# MB_ps_io.net
KiCad netlist of a schematic drawn in Altium Designer
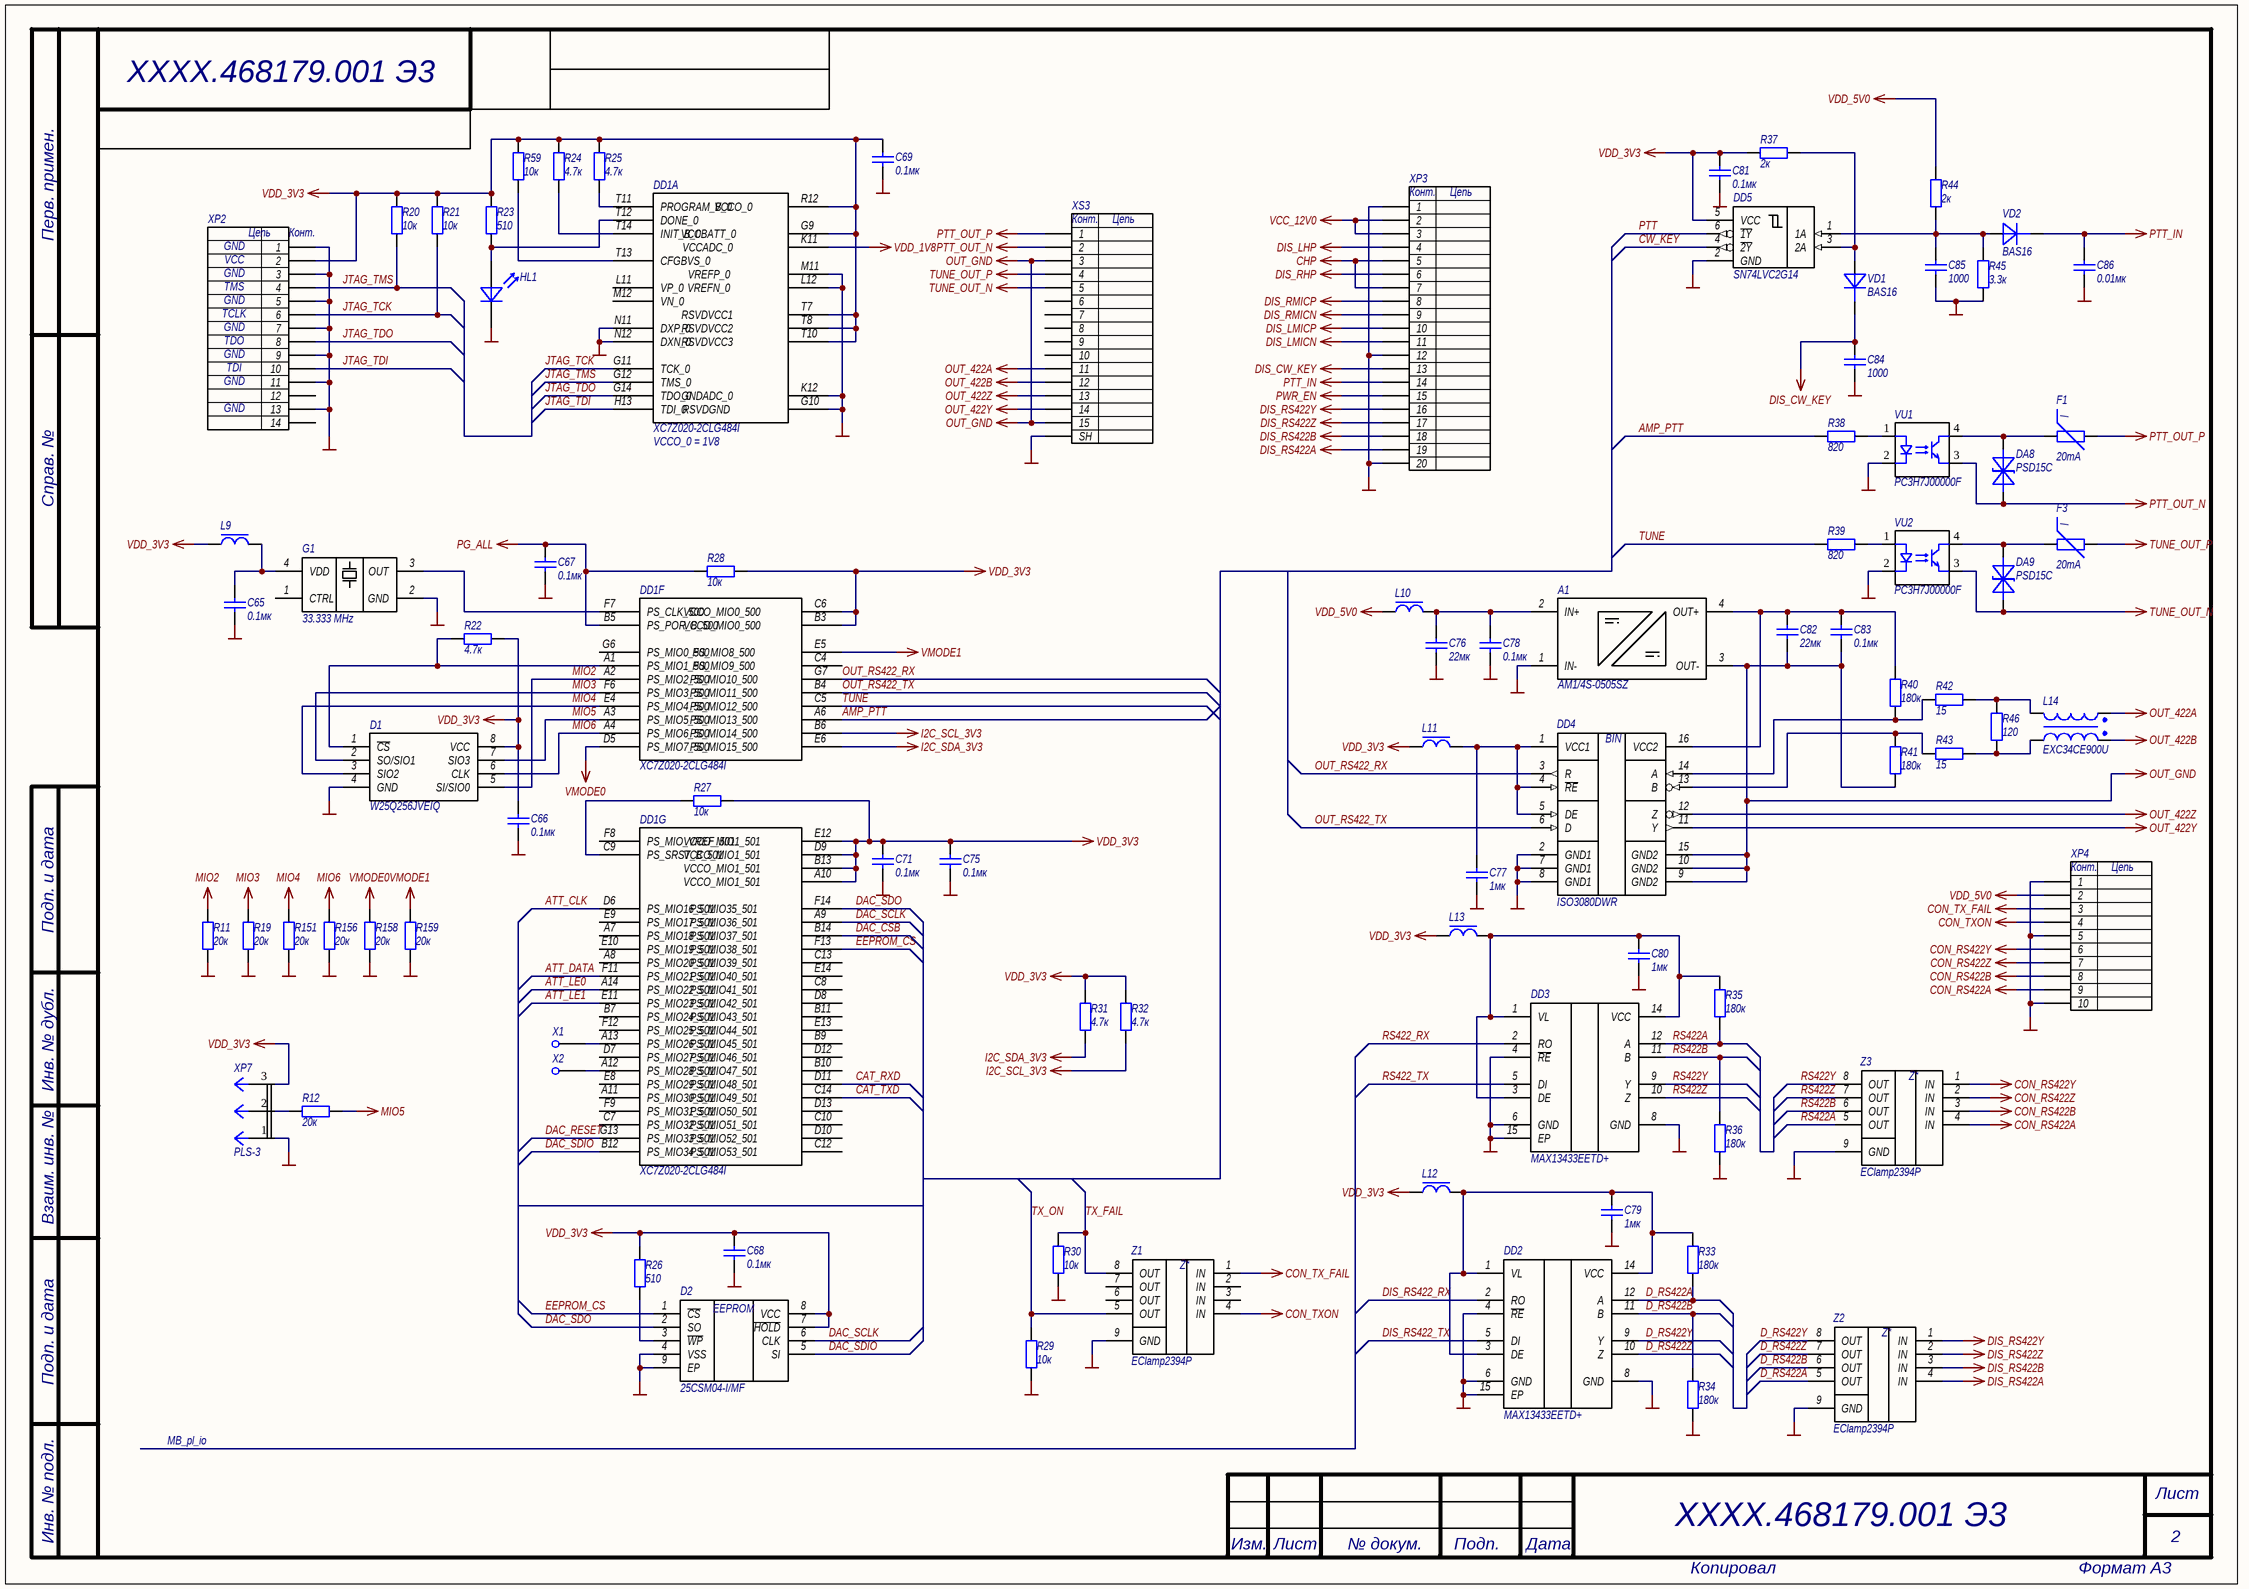
[diagram p0: MB_ps_io.SchDoc]

(export (version "E")
  (design (tool "Eeschema 10.0.6"))
  (components
    (comp (ref "A1")
      (value "AM1/4S-0505SZ")
      (footprint "Series AM1/4S-Z")
      (description "0.25 Watt ¦ DC-DC Converter")
      (fields (field (name "MANUFACTURER") "flex"))
      (libsource (lib "nels_other") (part "Модуль AM1/4S-0505SZ"))
    )
    (comp (ref "C65")
      (value "0.1мк")
      (footprint "CAPC1005X06N")
      (description "Кер. ЧИП-конденсатор")
      (fields (field (name "TOLERANCE") "±10%"))
      (libsource (lib "nels") (part "Кер.ЧИП конд. 0402 0.1мкФ X7R 10%, 16В"))
    )
    (comp (ref "C66")
      (value "0.1мк")
      (footprint "CAPC1005X06N")
      (description "Кер. ЧИП-конденсатор")
      (fields (field (name "TOLERANCE") "±10%"))
      (libsource (lib "nels") (part "Кер.ЧИП конд. 0402 0.1мкФ X7R 10%, 16В"))
    )
    (comp (ref "C67")
      (value "0.1мк")
      (footprint "CAPC1005X06N")
      (description "Кер. ЧИП-конденсатор")
      (fields (field (name "TOLERANCE") "±10%"))
      (libsource (lib "nels") (part "Кер.ЧИП конд. 0402 0.1мкФ X7R 10%, 16В"))
    )
    (comp (ref "C68")
      (value "0.1мк")
      (footprint "CAPC1005X06N")
      (description "Кер. ЧИП-конденсатор")
      (fields (field (name "TOLERANCE") "±10%"))
      (libsource (lib "nels") (part "Кер.ЧИП конд. 0402 0.1мкФ X7R 10%, 16В"))
    )
    (comp (ref "C69")
      (value "0.1мк")
      (footprint "CAPC1005X06N")
      (description "Кер. ЧИП-конденсатор")
      (fields (field (name "TOLERANCE") "±10%"))
      (libsource (lib "nels") (part "Кер.ЧИП конд. 0402 0.1мкФ X7R 10%, 16В"))
    )
    (comp (ref "C71")
      (value "0.1мк")
      (footprint "CAPC1005X06N")
      (description "Кер. ЧИП-конденсатор")
      (fields (field (name "TOLERANCE") "±10%"))
      (libsource (lib "nels") (part "Кер.ЧИП конд. 0402 0.1мкФ X7R 10%, 16В"))
    )
    (comp (ref "C75")
      (value "0.1мк")
      (footprint "CAPC1005X06N")
      (description "Кер. ЧИП-конденсатор")
      (fields (field (name "TOLERANCE") "±10%"))
      (libsource (lib "nels") (part "Кер.ЧИП конд. 0402 0.1мкФ X7R 10%, 16В"))
    )
    (comp (ref "C76")
      (value "22мк")
      (footprint "CAPC2012X12L")
      (description "Кер. ЧИП-конденсатор")
      (fields (field (name "MANUFACTURER") "TDK") (field (name "TOLERANCE") "±10%"))
      (libsource (lib "nels_caps") (part "Кер.ЧИП конд. 0805 22мкФ X5R 10% 16В"))
    )
    (comp (ref "C77")
      (value "1мк")
      (footprint "CAPC1005X06N")
      (description "Кер. ЧИП-конденсатор")
      (fields (field (name "TOLERANCE") "±10%"))
      (libsource (lib "nels_caps") (part "Кер.ЧИП конд. 0402 1мкФ X5R 10%, 10В"))
    )
    (comp (ref "C78")
      (value "0.1мк")
      (footprint "CAPC1005X06N")
      (description "Кер. ЧИП-конденсатор")
      (fields (field (name "TOLERANCE") "±10%"))
      (libsource (lib "nels") (part "Кер.ЧИП конд. 0402 0.1мкФ X7R 10%, 16В"))
    )
    (comp (ref "C79")
      (value "1мк")
      (footprint "CAPC1005X06N")
      (description "Кер. ЧИП-конденсатор")
      (fields (field (name "TOLERANCE") "±10%"))
      (libsource (lib "nels_caps") (part "Кер.ЧИП конд. 0402 1мкФ X5R 10%, 10В"))
    )
    (comp (ref "C80")
      (value "1мк")
      (footprint "CAPC1005X06N")
      (description "Кер. ЧИП-конденсатор")
      (fields (field (name "TOLERANCE") "±10%"))
      (libsource (lib "nels_caps") (part "Кер.ЧИП конд. 0402 1мкФ X5R 10%, 10В"))
    )
    (comp (ref "C81")
      (value "0.1мк")
      (footprint "CAPC1005X06N")
      (description "Кер. ЧИП-конденсатор")
      (fields (field (name "TOLERANCE") "±10%"))
      (libsource (lib "nels") (part "Кер.ЧИП конд. 0402 0.1мкФ X7R 10%, 16В"))
    )
    (comp (ref "C82")
      (value "22мк")
      (footprint "CAPC2012X12L")
      (description "Кер. ЧИП-конденсатор")
      (fields (field (name "MANUFACTURER") "TDK") (field (name "TOLERANCE") "±10%"))
      (libsource (lib "nels_caps") (part "Кер.ЧИП конд. 0805 22мкФ X5R 10% 16В"))
    )
    (comp (ref "C83")
      (value "0.1мк")
      (footprint "CAPC1005X06N")
      (description "Кер. ЧИП-конденсатор")
      (fields (field (name "TOLERANCE") "±10%"))
      (libsource (lib "nels") (part "Кер.ЧИП конд. 0402 0.1мкФ X7R 10%, 16В"))
    )
    (comp (ref "C84")
      (value "1000")
      (footprint "CAPC1005X06N")
      (description "Кер. ЧИП-конденсатор")
      (fields (field (name "TOLERANCE") "±5%"))
      (libsource (lib "nels_caps") (part "Кер.ЧИП конд. 0402 1000пФ NP0 5%, 50В"))
    )
    (comp (ref "C85")
      (value "1000")
      (footprint "CAPC1005X06N")
      (description "Кер. ЧИП-конденсатор")
      (fields (field (name "TOLERANCE") "±5%"))
      (libsource (lib "nels_caps") (part "Кер.ЧИП конд. 0402 1000пФ NP0 5%, 50В"))
    )
    (comp (ref "C86")
      (value "0.01мк")
      (footprint "CAPC1005X06N")
      (description "Кер. ЧИП-конденсатор")
      (fields (field (name "TOLERANCE") "±20%"))
      (libsource (lib "nels_caps") (part "Кер.ЧИП конд. 0402 0.01мкФ X7R 10%, 50В"))
    )
    (comp (ref "D1")
      (value "W25Q256JVEIQ")
      (footprint "SON127P800X70_HS-9N")
      (description "3V 256M-BIT SERIAL FLASH MEMORY WITH DUAL/QUAD SPI")
      (fields (field (name "MANUFACTURER") "WINBOND"))
      (libsource (lib "nels_chip") (part "Микросхема W25Q256JVEIQ"))
    )
    (comp (ref "D2")
      (value "25CSM04-I/MF")
      (footprint "SON127P600X80_HS-9N")
      (description "4-Mbit SPI Serial EEPROM with 128-Bit Serial Number and Enhanced Write Protection")
      (fields (field (name "MANUFACTURER") "MICROCHIP"))
      (libsource (lib "nels_chip") (part "Микросхема 25CSM04-I/MF"))
    )
    (comp (ref "DA8")
      (value "PSD15C")
      (footprint "SOT0P254X110-2N")
      (description "HIGH POWERED TVS")
      (fields (field (name "MANUFACTURER") "PROTEK"))
      (libsource (lib "nels_other") (part "ЧИП защитный диод PSD15C"))
    )
    (comp (ref "DA9")
      (value "PSD15C")
      (footprint "SOT0P254X110-2N")
      (description "HIGH POWERED TVS")
      (fields (field (name "MANUFACTURER") "PROTEK"))
      (libsource (lib "nels_other") (part "ЧИП защитный диод PSD15C"))
    )
    (comp (ref "DD1")
      (value "XC7Z020-2CLG484I")
      (footprint "BGA484C80P22X22_1900X1900X160")
      (description "Zynq®-7000 SoC Family")
      (fields (field (name "MANUFACTURER") "XILINX"))
      (libsource (lib "MB") (part "Микросхема XC7Z020-2CLG484I"))
    )
    (comp (ref "DD2")
      (value "MAX13433EETD+")
      (footprint "SON40P300X80_HS-15L")
      (description "RS-422 Transceivers with Low-Voltage Logic Interface 16M")
      (fields (field (name "MANUFACTURER") "Maxim"))
      (libsource (lib "nels_chip") (part "Микросхема MAX13433EETD+"))
    )
    (comp (ref "DD3")
      (value "MAX13433EETD+")
      (footprint "SON40P300X80_HS-15L")
      (description "RS-422 Transceivers with Low-Voltage Logic Interface 16M")
      (fields (field (name "MANUFACTURER") "Maxim"))
      (libsource (lib "nels_chip") (part "Микросхема MAX13433EETD+"))
    )
    (comp (ref "DD4")
      (value "ISO3080DWR")
      (footprint "SOIC127P1030X265-16N")
      (description "ISOLATED 5-V FULL DUPLEX RS-485 TRANSCEIVERS 200 kbps")
      (fields (field (name "MANUFACTURER") "TI"))
      (libsource (lib "nels_chip") (part "Микросхема ISO3080DWR"))
    )
    (comp (ref "DD5")
      (value "SN74LVC2G14")
      (footprint "SOT65P210X110-6L")
      (description "Dual Schmitt-Trigger Inverter")
      (fields (field (name "MANUFACTURER") "TI"))
      (libsource (lib "nels_chip") (part "Микросхема SN74LVC2G14DCKR"))
    )
    (comp (ref "F1")
      (value "20mA")
      (footprint "FUSC1607X85N")
      (description "ЧИП-резистор")
      (fields (field (name "MANUFACTURER") "Belfuse") (field (name "MANUFACTURERPARTNUMBER") "0ZCM0002FF2G"))
      (libsource (lib "nels_other") (part "Чип предохранитель 0ZCM0002FF2G"))
    )
    (comp (ref "F3")
      (value "20mA")
      (footprint "FUSC1607X85N")
      (description "ЧИП-резистор")
      (fields (field (name "MANUFACTURER") "Belfuse") (field (name "MANUFACTURERPARTNUMBER") "0ZCM0002FF2G"))
      (libsource (lib "nels_other") (part "Чип предохранитель 0ZCM0002FF2G"))
    )
    (comp (ref "G1")
      (value "33.333 MHz")
      (footprint "XTAL_ASFLMB-33.333MHZ-LC-T")
      (description "33.333 MHz HCMOS/TTL Clock Oscillator")
      (fields (field (name "MANUFACTURER") "Abracom"))
      (libsource (lib "nels_other") (part "Генератор кварцевый ASFLMB-33.333MHZ"))
    )
    (comp (ref "HL1")
      (value "~")
      (footprint "CD1608-0603_GREEN")
      (description "ЧИП-светодиод")
      (fields
        (field (name "MANUFACTURER") "FORYARD")
        (field (name "MANUFACTURERPARTNUMBER") "FYLS-0603UGC")
        (field (name "PUBLISHER") "Altium Limited")
      )
      (libsource (lib "nels_other") (part "Светодиод SMD FYLS-0603UGC (зеленый)"))
    )
    (comp (ref "L9")
      (value "BLM18PG121SN1D")
      (footprint "INDC1608X08L")
      (description "SMD EMI Suppression Filter EMIFIL")
      (fields (field (name "MANUFACTURER") "Murata"))
      (libsource (lib "nels_ind") (part "ЧИП дроссель 0603 BLM18PG121SN1D"))
    )
    (comp (ref "L10")
      (value "BLM18PG121SN1D")
      (footprint "INDC1608X08L")
      (description "SMD EMI Suppression Filter EMIFIL")
      (fields (field (name "MANUFACTURER") "Murata"))
      (libsource (lib "nels_ind") (part "ЧИП дроссель 0603 BLM18PG121SN1D"))
    )
    (comp (ref "L11")
      (value "BLM18PG121SN1D")
      (footprint "INDC1608X08L")
      (description "SMD EMI Suppression Filter EMIFIL")
      (fields (field (name "MANUFACTURER") "Murata"))
      (libsource (lib "nels_ind") (part "ЧИП дроссель 0603 BLM18PG121SN1D"))
    )
    (comp (ref "L12")
      (value "BLM18PG121SN1D")
      (footprint "INDC1608X08L")
      (description "SMD EMI Suppression Filter EMIFIL")
      (fields (field (name "MANUFACTURER") "Murata"))
      (libsource (lib "nels_ind") (part "ЧИП дроссель 0603 BLM18PG121SN1D"))
    )
    (comp (ref "L13")
      (value "BLM18PG121SN1D")
      (footprint "INDC1608X08L")
      (description "SMD EMI Suppression Filter EMIFIL")
      (fields (field (name "MANUFACTURER") "Murata"))
      (libsource (lib "nels_ind") (part "ЧИП дроссель 0603 BLM18PG121SN1D"))
    )
    (comp (ref "L14")
      (value "EXC34CE900U")
      (footprint "EXC34CE900U")
      (description "Common Mode Noise Filters EXC34CG/CE type")
      (fields (field (name "MANUFACTURER") "Panasonic"))
      (libsource (lib "nels_ind") (part "ЧИП синфазный фильтр 0805 EXC34CE900U"))
    )
    (comp (ref "R11")
      (value "20к")
      (footprint "RESC1005X06N")
      (description "ЧИП-резистор")
      (fields (field (name "TOLERANCE") "±5%"))
      (libsource (lib "nels_res") (part "Чип резистор 0402 20 кОм, 5%"))
    )
    (comp (ref "R12")
      (value "20к")
      (footprint "RESC1005X06N")
      (description "ЧИП-резистор")
      (fields (field (name "TOLERANCE") "±5%"))
      (libsource (lib "") (part "Чип резистор 0402 20 кОм, 5%_1"))
    )
    (comp (ref "R19")
      (value "20к")
      (footprint "RESC1005X06N")
      (description "ЧИП-резистор")
      (fields (field (name "TOLERANCE") "±5%"))
      (libsource (lib "nels_res") (part "Чип резистор 0402 20 кОм, 5%"))
    )
    (comp (ref "R20")
      (value "10к")
      (footprint "RESC1005X06N")
      (description "ЧИП-резистор")
      (fields (field (name "TOLERANCE") "±5%"))
      (libsource (lib "") (part "Чип резистор 0402 10 кОм, 5%_2"))
    )
    (comp (ref "R21")
      (value "10к")
      (footprint "RESC1005X06N")
      (description "ЧИП-резистор")
      (fields (field (name "TOLERANCE") "±5%"))
      (libsource (lib "") (part "Чип резистор 0402 10 кОм, 5%_2"))
    )
    (comp (ref "R22")
      (value "4.7к")
      (footprint "RESC1005X06N")
      (description "ЧИП-резистор")
      (fields (field (name "TOLERANCE") "±5%"))
      (libsource (lib "nels_res") (part "Чип резистор 0402 4,7 кОм, 5%"))
    )
    (comp (ref "R23")
      (value "510")
      (footprint "RESC1005X06N")
      (description "ЧИП-резистор")
      (fields (field (name "TOLERANCE") "±5%"))
      (libsource (lib "nels_res") (part "Чип резистор 0402 510 Ом, 5%"))
    )
    (comp (ref "R24")
      (value "4.7к")
      (footprint "RESC1005X06N")
      (description "ЧИП-резистор")
      (fields (field (name "TOLERANCE") "±1%"))
      (libsource (lib "nels_res") (part "Чип резистор 0402 4,7 кОм, 1%"))
    )
    (comp (ref "R25")
      (value "4.7к")
      (footprint "RESC1005X06N")
      (description "ЧИП-резистор")
      (fields (field (name "TOLERANCE") "±1%"))
      (libsource (lib "nels_res") (part "Чип резистор 0402 4,7 кОм, 1%"))
    )
    (comp (ref "R26")
      (value "510")
      (footprint "RESC1005X06N")
      (description "ЧИП-резистор")
      (fields (field (name "TOLERANCE") "±5%"))
      (libsource (lib "nels_res") (part "Чип резистор 0402 510 Ом, 5%"))
    )
    (comp (ref "R27")
      (value "10к")
      (footprint "RESC1005X06N")
      (description "ЧИП-резистор")
      (fields (field (name "TOLERANCE") "±5%"))
      (libsource (lib "") (part "Чип резистор 0402 10 кОм, 5%_1"))
    )
    (comp (ref "R28")
      (value "10к")
      (footprint "RESC1005X06N")
      (description "ЧИП-резистор")
      (fields (field (name "TOLERANCE") "±5%"))
      (libsource (lib "") (part "Чип резистор 0402 10 кОм, 5%_1"))
    )
    (comp (ref "R29")
      (value "10к")
      (footprint "RESC1005X06N")
      (description "ЧИП-резистор")
      (fields (field (name "TOLERANCE") "±5%"))
      (libsource (lib "nels") (part "Чип резистор 0402 10 кОм, 5%"))
    )
    (comp (ref "R30")
      (value "10к")
      (footprint "RESC1005X06N")
      (description "ЧИП-резистор")
      (fields (field (name "TOLERANCE") "±5%"))
      (libsource (lib "nels") (part "Чип резистор 0402 10 кОм, 5%"))
    )
    (comp (ref "R31")
      (value "4.7к")
      (footprint "RESC1005X06N")
      (description "ЧИП-резистор")
      (fields (field (name "TOLERANCE") "±5%"))
      (libsource (lib "") (part "Чип резистор 0402 4,7 кОм, 5%_1"))
    )
    (comp (ref "R32")
      (value "4.7к")
      (footprint "RESC1005X06N")
      (description "ЧИП-резистор")
      (fields (field (name "TOLERANCE") "±5%"))
      (libsource (lib "") (part "Чип резистор 0402 4,7 кОм, 5%_1"))
    )
    (comp (ref "R33")
      (value "180к")
      (footprint "RESC1005X06N")
      (description "ЧИП-резистор")
      (fields (field (name "TOLERANCE") "±5%"))
      (libsource (lib "nels") (part "Чип резистор 0402 180 кОм, 5%"))
    )
    (comp (ref "R34")
      (value "180к")
      (footprint "RESC1005X06N")
      (description "ЧИП-резистор")
      (fields (field (name "TOLERANCE") "±5%"))
      (libsource (lib "nels") (part "Чип резистор 0402 180 кОм, 5%"))
    )
    (comp (ref "R35")
      (value "180к")
      (footprint "RESC1005X06N")
      (description "ЧИП-резистор")
      (fields (field (name "TOLERANCE") "±5%"))
      (libsource (lib "nels") (part "Чип резистор 0402 180 кОм, 5%"))
    )
    (comp (ref "R36")
      (value "180к")
      (footprint "RESC1005X06N")
      (description "ЧИП-резистор")
      (fields (field (name "TOLERANCE") "±5%"))
      (libsource (lib "nels") (part "Чип резистор 0402 180 кОм, 5%"))
    )
    (comp (ref "R37")
      (value "2к")
      (footprint "RESC1005X06N")
      (description "ЧИП-резистор")
      (fields (field (name "TOLERANCE") "±5%"))
      (libsource (lib "") (part "Чип резистор 0402 2 кОм, 5%_1"))
    )
    (comp (ref "R38")
      (value "820")
      (footprint "RESC1005X06N")
      (description "ЧИП-резистор")
      (fields (field (name "TOLERANCE") "±5%"))
      (libsource (lib "nels_res") (part "Чип резистор 0402 820 Ом, 5%"))
    )
    (comp (ref "R39")
      (value "820")
      (footprint "RESC1005X06N")
      (description "ЧИП-резистор")
      (fields (field (name "TOLERANCE") "±5%"))
      (libsource (lib "nels_res") (part "Чип резистор 0402 820 Ом, 5%"))
    )
    (comp (ref "R40")
      (value "180к")
      (footprint "RESC1005X06N")
      (description "ЧИП-резистор")
      (fields (field (name "TOLERANCE") "±5%"))
      (libsource (lib "nels") (part "Чип резистор 0402 180 кОм, 5%"))
    )
    (comp (ref "R41")
      (value "180к")
      (footprint "RESC1005X06N")
      (description "ЧИП-резистор")
      (fields (field (name "TOLERANCE") "±5%"))
      (libsource (lib "nels") (part "Чип резистор 0402 180 кОм, 5%"))
    )
    (comp (ref "R42")
      (value "15")
      (footprint "RESC1005X06N")
      (description "ЧИП-резистор")
      (fields (field (name "TOLERANCE") "±5%"))
      (libsource (lib "nels") (part "Чип резистор 0402 15 Ом, 5%"))
    )
    (comp (ref "R43")
      (value "15")
      (footprint "RESC1005X06N")
      (description "ЧИП-резистор")
      (fields (field (name "TOLERANCE") "±5%"))
      (libsource (lib "nels") (part "Чип резистор 0402 15 Ом, 5%"))
    )
    (comp (ref "R44")
      (value "2к")
      (footprint "RESC1005X06N")
      (description "ЧИП-резистор")
      (fields (field (name "TOLERANCE") "±5%"))
      (libsource (lib "nels_res") (part "Чип резистор 0402 2 кОм, 5%"))
    )
    (comp (ref "R45")
      (value "3.3к")
      (footprint "RESC1005X06N")
      (description "ЧИП-резистор")
      (fields (field (name "TOLERANCE") "±5%"))
      (libsource (lib "nels_res") (part "Чип резистор 0402 3,3 кОм, 5%"))
    )
    (comp (ref "R46")
      (value "120")
      (footprint "RESC1005X06N")
      (description "ЧИП-резистор")
      (fields (field (name "TOLERANCE") "±5%"))
      (libsource (lib "nels") (part "Чип резистор 0402 120 Ом, 5%"))
    )
    (comp (ref "R59")
      (value "10к")
      (footprint "RESC1005X06N")
      (description "ЧИП-резистор")
      (fields (field (name "TOLERANCE") "±5%"))
      (libsource (lib "nels") (part "Чип резистор 0402 10 кОм, 5%"))
    )
    (comp (ref "R151")
      (value "20к")
      (footprint "RESC1005X06N")
      (description "ЧИП-резистор")
      (fields (field (name "TOLERANCE") "±5%"))
      (libsource (lib "nels_res") (part "Чип резистор 0402 20 кОм, 5%"))
    )
    (comp (ref "R156")
      (value "20к")
      (footprint "RESC1005X06N")
      (description "ЧИП-резистор")
      (fields (field (name "TOLERANCE") "±5%"))
      (libsource (lib "nels_res") (part "Чип резистор 0402 20 кОм, 5%"))
    )
    (comp (ref "R158")
      (value "20к")
      (footprint "RESC1005X06N")
      (description "ЧИП-резистор")
      (fields (field (name "TOLERANCE") "±5%"))
      (libsource (lib "nels_res") (part "Чип резистор 0402 20 кОм, 5%"))
    )
    (comp (ref "R159")
      (value "20к")
      (footprint "RESC1005X06N")
      (description "ЧИП-резистор")
      (fields (field (name "TOLERANCE") "±5%"))
      (libsource (lib "nels_res") (part "Чип резистор 0402 20 кОм, 5%"))
    )
    (comp (ref "VD1")
      (value "BAS16")
      (footprint "SOT23_N")
      (description "High-speed switching diodes")
      (fields (field (name "MANUFACTURER") "Nexperia"))
      (libsource (lib "nels_other") (part "ЧИП диод BAS16"))
    )
    (comp (ref "VD2")
      (value "BAS16")
      (footprint "SOT23_N")
      (description "High-speed switching diodes")
      (fields (field (name "MANUFACTURER") "Nexperia"))
      (libsource (lib "nels_other") (part "ЧИП диод BAS16"))
    )
    (comp (ref "VU1")
      (value "PC3H7J00000F")
      (footprint "SO4-170-1.27")
      (description "Mini-falt Package, General Purpose Half Pitch Photocouper")
      (libsource (lib "nels_other") (part "Оптопара транзисторная PC3H7J00000F"))
    )
    (comp (ref "VU2")
      (value "PC3H7J00000F")
      (footprint "SO4-170-1.27")
      (description "Mini-falt Package, General Purpose Half Pitch Photocouper")
      (libsource (lib "nels_other") (part "Оптопара транзисторная PC3H7J00000F"))
    )
    (comp (ref "X1")
      (value "Конструктивный элемент")
      (footprint "PIN2_PROBE")
      (description "Соединитель")
      (libsource (lib "nels_conn") (part "Соединение под пайку"))
    )
    (comp (ref "X2")
      (value "Конструктивный элемент")
      (footprint "PIN2_PROBE")
      (description "Соединитель")
      (libsource (lib "nels_conn") (part "Соединение под пайку"))
    )
    (comp (ref "XP2")
      (value "IDC2-14MS")
      (footprint "IDC2-14MS")
      (description "JTAG Xilinx IDC2-14MS")
      (fields (field (name "MANUFACTURER") "Molex"))
      (libsource (lib "nels") (part "Соединитель IDC2-14MS"))
    )
    (comp (ref "XP3")
      (value "FH12-20S-0.5SVA")
      (footprint "FH12-20S-0.5SVA")
      (description "FPC Connectors, Flex-to-Board, 20 Position, .5mm [.02in]")
      (libsource (lib "nels_conn") (part "Соединитель FH12-20S-0.5SVA"))
    )
    (comp (ref "XP4")
      (value "FH12-10S-0.5SVA")
      (footprint "FH12-10S-0.5SH")
      (description "0.5mm  Pitch FPC/FFC Connector FH12 Series")
      (fields (field (name "MANUFACTURER") "Hirose"))
      (libsource (lib "nels_conn") (part "Соединитель FH12-10S-0.5SVA"))
    )
    (comp (ref "XP7")
      (value "PLS-3")
      (footprint "PLS-3 (DS1021-1x3)")
      (description "Вилка штыревая 2.54мм 1x3 прямая тип1")
      (libsource (lib "nels_conn") (part "Соединитель PLS-3 (DS1021-1x3)"))
    )
    (comp (ref "XS3")
      (value "DS1038-15F")
      (footprint "DS1038-15F")
      (description "Гнездо 15 pin высокой плотности на плату")
      (fields (field (name "MANUFACTURER") "Connfly"))
      (libsource (lib "nels_conn") (part "Соединитель DHR-15FB (DS1038-15F)"))
    )
    (comp (ref "Z1")
      (value "EClamp2394P")
      (footprint "SON50P160X65_HS-9N")
      (description "ESD/EMI Protection  for Color LCD Interfaces")
      (fields (field (name "MANUFACTURER") "SEMTECH"))
      (libsource (lib "nels_other") (part "Фильтр EMI EClamp2394P"))
    )
    (comp (ref "Z2")
      (value "EClamp2394P")
      (footprint "SON50P160X65_HS-9N")
      (description "ESD/EMI Protection  for Color LCD Interfaces")
      (fields (field (name "MANUFACTURER") "SEMTECH"))
      (libsource (lib "nels_other") (part "Фильтр EMI EClamp2394P"))
    )
    (comp (ref "Z3")
      (value "EClamp2394P")
      (footprint "SON50P160X65_HS-9N")
      (description "ESD/EMI Protection  for Color LCD Interfaces")
      (fields (field (name "MANUFACTURER") "SEMTECH"))
      (libsource (lib "nels_other") (part "Фильтр EMI EClamp2394P"))
    )
  )
  (nets
    (net (code "1") (name "/AMP_PTT") (class "Default")
      (node (ref "DD1") (pin "A6") (pinfunction "PS_MIO13_500_A6") (pintype "passive"))
      (node (ref "R38") (pin "1") (pinfunction "1_1") (pintype "passive"))
    )
    (net (code "2") (name "/ATT_CLK") (class "Default")
      (node (ref "DD1") (pin "D6") (pinfunction "PS_MIO16_501_D6") (pintype "passive"))
    )
    (net (code "3") (name "/ATT_DATA") (class "Default")
      (node (ref "DD1") (pin "F11") (pinfunction "PS_MIO21_501_F11") (pintype "passive"))
    )
    (net (code "4") (name "/ATT_LE0") (class "Default")
      (node (ref "DD1") (pin "A14") (pinfunction "PS_MIO22_501_A14") (pintype "passive"))
    )
    (net (code "5") (name "/ATT_LE1") (class "Default")
      (node (ref "DD1") (pin "E11") (pinfunction "PS_MIO23_501_E11") (pintype "passive"))
    )
    (net (code "6") (name "/CAT_RXD") (class "Default")
      (node (ref "DD1") (pin "D11") (pinfunction "PS_MIO48_501_D11") (pintype "passive"))
    )
    (net (code "7") (name "/CAT_TXD") (class "Default")
      (node (ref "DD1") (pin "C14") (pinfunction "PS_MIO49_501_C14") (pintype "passive"))
    )
    (net (code "8") (name "/CW_KEY") (class "Default")
      (node (ref "DD5") (pin "4") (pinfunction "~{2Y}_4") (pintype "output"))
    )
    (net (code "9") (name "/DAC_CSB") (class "Default")
      (node (ref "DD1") (pin "B14") (pinfunction "PS_MIO37_501_B14") (pintype "passive"))
    )
    (net (code "10") (name "/DAC_RESET") (class "Default")
      (node (ref "DD1") (pin "G13") (pinfunction "PS_MIO33_501_G13") (pintype "passive"))
    )
    (net (code "11") (name "/DAC_SCLK") (class "Default")
      (node (ref "D2") (pin "6") (pinfunction "CLK_6") (pintype "passive"))
      (node (ref "DD1") (pin "A9") (pinfunction "PS_MIO36_501_A9") (pintype "passive"))
    )
    (net (code "12") (name "/DAC_SDIO") (class "Default")
      (node (ref "D2") (pin "5") (pinfunction "SI_5") (pintype "passive"))
      (node (ref "DD1") (pin "B12") (pinfunction "PS_MIO34_501_B12") (pintype "passive"))
    )
    (net (code "13") (name "/DAC_SDO") (class "Default")
      (node (ref "D2") (pin "2") (pinfunction "SO_2") (pintype "passive"))
      (node (ref "DD1") (pin "F14") (pinfunction "PS_MIO35_501_F14") (pintype "passive"))
    )
    (net (code "14") (name "/DIS_RS422_RX") (class "Default")
      (node (ref "DD2") (pin "2") (pinfunction "RO_2") (pintype "passive"))
    )
    (net (code "15") (name "/DIS_RS422_TX") (class "Default")
      (node (ref "DD2") (pin "5") (pinfunction "DI_5") (pintype "passive"))
    )
    (net (code "16") (name "/D_RS422A") (class "Default")
      (node (ref "DD2") (pin "12") (pinfunction "A_12") (pintype "passive"))
      (node (ref "R33") (pin "1") (pinfunction "1_1") (pintype "passive"))
      (node (ref "Z2") (pin "5") (pinfunction "OUT_5") (pintype "passive"))
    )
    (net (code "17") (name "/D_RS422B") (class "Default")
      (node (ref "DD2") (pin "11") (pinfunction "B_11") (pintype "passive"))
      (node (ref "R34") (pin "2") (pinfunction "2_2") (pintype "passive"))
      (node (ref "Z2") (pin "6") (pinfunction "OUT_6") (pintype "passive"))
    )
    (net (code "18") (name "/D_RS422Y") (class "Default")
      (node (ref "DD2") (pin "9") (pinfunction "Y_9") (pintype "passive"))
      (node (ref "Z2") (pin "8") (pinfunction "OUT_8") (pintype "passive"))
    )
    (net (code "19") (name "/D_RS422Z") (class "Default")
      (node (ref "DD2") (pin "10") (pinfunction "Z_10") (pintype "passive"))
      (node (ref "Z2") (pin "7") (pinfunction "OUT_7") (pintype "passive"))
    )
    (net (code "20") (name "/EEPROM_CS") (class "Default")
      (node (ref "D2") (pin "1") (pinfunction "~{CS}_1") (pintype "passive"))
      (node (ref "DD1") (pin "F13") (pinfunction "PS_MIO38_501_F13") (pintype "passive"))
    )
    (net (code "21") (name "/JTAG_TCK") (class "Default")
      (node (ref "DD1") (pin "G11") (pinfunction "TCK_0_G11") (pintype "passive"))
      (node (ref "R21") (pin "2") (pinfunction "2_2") (pintype "passive"))
      (node (ref "XP2") (pin "6") (pinfunction "6_6") (pintype "passive"))
    )
    (net (code "22") (name "/JTAG_TDI") (class "Default")
      (node (ref "DD1") (pin "H13") (pinfunction "TDI_0_H13") (pintype "passive"))
      (node (ref "XP2") (pin "10") (pinfunction "10_10") (pintype "passive"))
    )
    (net (code "23") (name "/JTAG_TDO") (class "Default")
      (node (ref "DD1") (pin "G14") (pinfunction "TDO_0_G14") (pintype "passive"))
      (node (ref "XP2") (pin "8") (pinfunction "8_8") (pintype "passive"))
    )
    (net (code "24") (name "/JTAG_TMS") (class "Default")
      (node (ref "DD1") (pin "G12") (pinfunction "TMS_0_G12") (pintype "passive"))
      (node (ref "R20") (pin "2") (pinfunction "2_2") (pintype "passive"))
      (node (ref "XP2") (pin "4") (pinfunction "4_4") (pintype "passive"))
    )
    (net (code "25") (name "/OUT_RS422_RX") (class "Default")
      (node (ref "DD1") (pin "G7") (pinfunction "PS_MIO10_500_G7") (pintype "passive"))
      (node (ref "DD4") (pin "3") (pinfunction "R_3") (pintype "output"))
    )
    (net (code "26") (name "/OUT_RS422_TX") (class "Default")
      (node (ref "DD1") (pin "B4") (pinfunction "PS_MIO11_500_B4") (pintype "passive"))
      (node (ref "DD4") (pin "6") (pinfunction "D_6") (pintype "input"))
    )
    (net (code "27") (name "/PTT") (class "Default")
      (node (ref "DD5") (pin "6") (pinfunction "~{1Y}_6") (pintype "output"))
    )
    (net (code "28") (name "/RS422A") (class "Default")
      (node (ref "DD3") (pin "12") (pinfunction "A_12") (pintype "passive"))
      (node (ref "R35") (pin "1") (pinfunction "1_1") (pintype "passive"))
      (node (ref "Z3") (pin "5") (pinfunction "OUT_5") (pintype "passive"))
    )
    (net (code "29") (name "/RS422B") (class "Default")
      (node (ref "DD3") (pin "11") (pinfunction "B_11") (pintype "passive"))
      (node (ref "R36") (pin "2") (pinfunction "2_2") (pintype "passive"))
      (node (ref "Z3") (pin "6") (pinfunction "OUT_6") (pintype "passive"))
    )
    (net (code "30") (name "/RS422Y") (class "Default")
      (node (ref "DD3") (pin "9") (pinfunction "Y_9") (pintype "passive"))
      (node (ref "Z3") (pin "8") (pinfunction "OUT_8") (pintype "passive"))
    )
    (net (code "31") (name "/RS422Z") (class "Default")
      (node (ref "DD3") (pin "10") (pinfunction "Z_10") (pintype "passive"))
      (node (ref "Z3") (pin "7") (pinfunction "OUT_7") (pintype "passive"))
    )
    (net (code "32") (name "/RS422_RX") (class "Default")
      (node (ref "DD3") (pin "2") (pinfunction "RO_2") (pintype "passive"))
    )
    (net (code "33") (name "/RS422_TX") (class "Default")
      (node (ref "DD3") (pin "5") (pinfunction "DI_5") (pintype "passive"))
    )
    (net (code "34") (name "/TUNE") (class "Default")
      (node (ref "DD1") (pin "C5") (pinfunction "PS_MIO12_500_C5") (pintype "passive"))
      (node (ref "R39") (pin "1") (pinfunction "1_1") (pintype "passive"))
    )
    (net (code "35") (name "/TX_FAIL") (class "Default")
      (node (ref "R30") (pin "2") (pinfunction "2_2") (pintype "passive"))
      (node (ref "Z1") (pin "8") (pinfunction "OUT_8") (pintype "passive"))
    )
    (net (code "36") (name "/TX_ON") (class "Default")
      (node (ref "R29") (pin "2") (pinfunction "2_2") (pintype "passive"))
      (node (ref "Z1") (pin "5") (pinfunction "OUT_5") (pintype "passive"))
    )
    (net (code "37") (name "CHP") (class "Default")
      (node (ref "XP3") (pin "5") (pinfunction "5_5") (pintype "passive"))
      (node (ref "XP3") (pin "7") (pinfunction "7_7") (pintype "passive"))
    )
    (net (code "38") (name "CON_RS422A") (class "Default")
      (node (ref "XP4") (pin "9") (pinfunction "9_9") (pintype "passive"))
      (node (ref "Z3") (pin "4") (pinfunction "IN_4") (pintype "passive"))
    )
    (net (code "39") (name "CON_RS422B") (class "Default")
      (node (ref "XP4") (pin "8") (pinfunction "8_8") (pintype "passive"))
      (node (ref "Z3") (pin "3") (pinfunction "IN_3") (pintype "passive"))
    )
    (net (code "40") (name "CON_RS422Y") (class "Default")
      (node (ref "XP4") (pin "6") (pinfunction "6_6") (pintype "passive"))
      (node (ref "Z3") (pin "1") (pinfunction "IN_1") (pintype "passive"))
    )
    (net (code "41") (name "CON_RS422Z") (class "Default")
      (node (ref "XP4") (pin "7") (pinfunction "7_7") (pintype "passive"))
      (node (ref "Z3") (pin "2") (pinfunction "IN_2") (pintype "passive"))
    )
    (net (code "42") (name "CON_TXON") (class "Default")
      (node (ref "XP4") (pin "4") (pinfunction "4_4") (pintype "passive"))
      (node (ref "Z1") (pin "4") (pinfunction "IN_4") (pintype "passive"))
    )
    (net (code "43") (name "CON_TX_FAIL") (class "Default")
      (node (ref "XP4") (pin "3") (pinfunction "3_3") (pintype "passive"))
      (node (ref "Z1") (pin "1") (pinfunction "IN_1") (pintype "passive"))
    )
    (net (code "44") (name "DIS_CW_KEY") (class "Default")
      (node (ref "C84") (pin "2") (pinfunction "2_2") (pintype "passive"))
      (node (ref "VD1") (pin "3") (pinfunction "K_3") (pintype "passive"))
      (node (ref "XP3") (pin "13") (pinfunction "13_13") (pintype "passive"))
    )
    (net (code "45") (name "DIS_LHP") (class "Default")
      (node (ref "XP3") (pin "4") (pinfunction "4_4") (pintype "passive"))
    )
    (net (code "46") (name "DIS_LMICN") (class "Default")
      (node (ref "XP3") (pin "11") (pinfunction "11_11") (pintype "passive"))
    )
    (net (code "47") (name "DIS_LMICP") (class "Default")
      (node (ref "XP3") (pin "10") (pinfunction "10_10") (pintype "passive"))
    )
    (net (code "48") (name "DIS_RHP") (class "Default")
      (node (ref "XP3") (pin "6") (pinfunction "6_6") (pintype "passive"))
    )
    (net (code "49") (name "DIS_RMICN") (class "Default")
      (node (ref "XP3") (pin "9") (pinfunction "9_9") (pintype "passive"))
    )
    (net (code "50") (name "DIS_RMICP") (class "Default")
      (node (ref "XP3") (pin "8") (pinfunction "8_8") (pintype "passive"))
    )
    (net (code "51") (name "DIS_RS422A") (class "Default")
      (node (ref "XP3") (pin "19") (pinfunction "19_19") (pintype "passive"))
      (node (ref "Z2") (pin "4") (pinfunction "IN_4") (pintype "passive"))
    )
    (net (code "52") (name "DIS_RS422B") (class "Default")
      (node (ref "XP3") (pin "18") (pinfunction "18_18") (pintype "passive"))
      (node (ref "Z2") (pin "3") (pinfunction "IN_3") (pintype "passive"))
    )
    (net (code "53") (name "DIS_RS422Y") (class "Default")
      (node (ref "XP3") (pin "16") (pinfunction "16_16") (pintype "passive"))
      (node (ref "Z2") (pin "1") (pinfunction "IN_1") (pintype "passive"))
    )
    (net (code "54") (name "DIS_RS422Z") (class "Default")
      (node (ref "XP3") (pin "17") (pinfunction "17_17") (pintype "passive"))
      (node (ref "Z2") (pin "2") (pinfunction "IN_2") (pintype "passive"))
    )
    (net (code "55") (name "GND") (class "Default")
      (node (ref "A1") (pin "1") (pinfunction "IN-_1") (pintype "passive"))
      (node (ref "C65") (pin "1") (pinfunction "1_1") (pintype "passive"))
      (node (ref "C66") (pin "1") (pinfunction "1_1") (pintype "passive"))
      (node (ref "C67") (pin "1") (pinfunction "1_1") (pintype "passive"))
      (node (ref "C68") (pin "1") (pinfunction "1_1") (pintype "passive"))
      (node (ref "C69") (pin "1") (pinfunction "1_1") (pintype "passive"))
      (node (ref "C71") (pin "1") (pinfunction "1_1") (pintype "passive"))
      (node (ref "C75") (pin "1") (pinfunction "1_1") (pintype "passive"))
      (node (ref "C76") (pin "1") (pinfunction "1_1") (pintype "passive"))
      (node (ref "C77") (pin "1") (pinfunction "1_1") (pintype "passive"))
      (node (ref "C78") (pin "1") (pinfunction "1_1") (pintype "passive"))
      (node (ref "C79") (pin "1") (pinfunction "1_1") (pintype "passive"))
      (node (ref "C80") (pin "1") (pinfunction "1_1") (pintype "passive"))
      (node (ref "C81") (pin "1") (pinfunction "1_1") (pintype "passive"))
      (node (ref "C84") (pin "1") (pinfunction "1_1") (pintype "passive"))
      (node (ref "C85") (pin "1") (pinfunction "1_1") (pintype "passive"))
      (node (ref "C86") (pin "1") (pinfunction "1_1") (pintype "passive"))
      (node (ref "D1") (pin "4") (pinfunction "GND_4") (pintype "passive"))
      (node (ref "D2") (pin "4") (pinfunction "VSS_4") (pintype "passive"))
      (node (ref "D2") (pin "9") (pinfunction "EP_9") (pintype "passive"))
      (node (ref "DD1") (pin "G10") (pinfunction "RSVDGND_G10") (pintype "passive"))
      (node (ref "DD1") (pin "K12") (pinfunction "GNDADC_0_K12") (pintype "passive"))
      (node (ref "DD1") (pin "L12") (pinfunction "VREFN_0_L12") (pintype "passive"))
      (node (ref "DD1") (pin "M11") (pinfunction "VREFP_0_M11") (pintype "passive"))
      (node (ref "DD1") (pin "N11") (pinfunction "DXP_0_N11") (pintype "passive"))
      (node (ref "DD1") (pin "N12") (pinfunction "DXN_0_N12") (pintype "passive"))
      (node (ref "DD2") (pin "15") (pinfunction "EP_15") (pintype "passive"))
      (node (ref "DD2") (pin "4") (pinfunction "~{RE}_4") (pintype "passive"))
      (node (ref "DD2") (pin "6") (pinfunction "GND_6") (pintype "passive"))
      (node (ref "DD2") (pin "8") (pinfunction "GND_8") (pintype "passive"))
      (node (ref "DD3") (pin "15") (pinfunction "EP_15") (pintype "passive"))
      (node (ref "DD3") (pin "4") (pinfunction "~{RE}_4") (pintype "passive"))
      (node (ref "DD3") (pin "6") (pinfunction "GND_6") (pintype "passive"))
      (node (ref "DD3") (pin "8") (pinfunction "GND_8") (pintype "passive"))
      (node (ref "DD4") (pin "2") (pinfunction "GND1_2") (pintype "passive"))
      (node (ref "DD4") (pin "7") (pinfunction "GND1_7") (pintype "passive"))
      (node (ref "DD4") (pin "8") (pinfunction "GND1_8") (pintype "passive"))
      (node (ref "DD5") (pin "2") (pinfunction "GND_2") (pintype "passive"))
      (node (ref "G1") (pin "2") (pinfunction "GND_2") (pintype "passive"))
      (node (ref "HL1") (pin "2") (pinfunction "K_2") (pintype "passive"))
      (node (ref "R11") (pin "1") (pinfunction "1_1") (pintype "passive"))
      (node (ref "R151") (pin "1") (pinfunction "1_1") (pintype "passive"))
      (node (ref "R156") (pin "1") (pinfunction "1_1") (pintype "passive"))
      (node (ref "R158") (pin "1") (pinfunction "1_1") (pintype "passive"))
      (node (ref "R159") (pin "1") (pinfunction "1_1") (pintype "passive"))
      (node (ref "R19") (pin "1") (pinfunction "1_1") (pintype "passive"))
      (node (ref "R29") (pin "1") (pinfunction "1_1") (pintype "passive"))
      (node (ref "R30") (pin "1") (pinfunction "1_1") (pintype "passive"))
      (node (ref "R34") (pin "1") (pinfunction "1_1") (pintype "passive"))
      (node (ref "R36") (pin "1") (pinfunction "1_1") (pintype "passive"))
      (node (ref "R45") (pin "2") (pinfunction "2_2") (pintype "passive"))
      (node (ref "VU1") (pin "2") (pinfunction "K_2") (pintype "passive"))
      (node (ref "VU2") (pin "2") (pinfunction "K_2") (pintype "passive"))
      (node (ref "XP2") (pin "1") (pinfunction "1_1") (pintype "passive"))
      (node (ref "XP2") (pin "11") (pinfunction "11_11") (pintype "passive"))
      (node (ref "XP2") (pin "13") (pinfunction "13_13") (pintype "passive"))
      (node (ref "XP2") (pin "3") (pinfunction "3_3") (pintype "passive"))
      (node (ref "XP2") (pin "5") (pinfunction "5_5") (pintype "passive"))
      (node (ref "XP2") (pin "7") (pinfunction "7_7") (pintype "passive"))
      (node (ref "XP2") (pin "9") (pinfunction "9_9") (pintype "passive"))
      (node (ref "XP3") (pin "1") (pinfunction "1_1") (pintype "passive"))
      (node (ref "XP3") (pin "12") (pinfunction "12_12") (pintype "passive"))
      (node (ref "XP3") (pin "20") (pinfunction "20_20") (pintype "passive"))
      (node (ref "XP4") (pin "1") (pinfunction "1_1") (pintype "passive"))
      (node (ref "XP4") (pin "10") (pinfunction "10_10") (pintype "passive"))
      (node (ref "XP4") (pin "5") (pinfunction "5_5") (pintype "passive"))
      (node (ref "XP7") (pin "1") (pinfunction "1_1") (pintype "passive"))
      (node (ref "XS3") (pin "16") (pinfunction "SH_16") (pintype "passive"))
      (node (ref "Z1") (pin "9") (pinfunction "GND_9") (pintype "passive"))
      (node (ref "Z2") (pin "9") (pinfunction "GND_9") (pintype "passive"))
      (node (ref "Z3") (pin "9") (pinfunction "GND_9") (pintype "passive"))
    )
    (net (code "56") (name "I2C_SCL_3V3") (class "Default")
      (node (ref "DD1") (pin "B6") (pinfunction "PS_MIO14_500_B6") (pintype "passive"))
      (node (ref "R32") (pin "2") (pinfunction "2_2") (pintype "passive"))
    )
    (net (code "57") (name "I2C_SDA_3V3") (class "Default")
      (node (ref "DD1") (pin "E6") (pinfunction "PS_MIO15_500_E6") (pintype "passive"))
      (node (ref "R31") (pin "2") (pinfunction "2_2") (pintype "passive"))
    )
    (net (code "58") (name "MIO2") (class "Default")
      (node (ref "D1") (pin "5") (pinfunction "SI/SIO0_5") (pintype "passive"))
      (node (ref "DD1") (pin "A2") (pinfunction "PS_MIO2_500_A2") (pintype "passive"))
      (node (ref "R11") (pin "2") (pinfunction "2_2") (pintype "passive"))
    )
    (net (code "59") (name "MIO3") (class "Default")
      (node (ref "D1") (pin "2") (pinfunction "SO/SIO1_2") (pintype "passive"))
      (node (ref "DD1") (pin "F6") (pinfunction "PS_MIO3_500_F6") (pintype "passive"))
      (node (ref "R19") (pin "2") (pinfunction "2_2") (pintype "passive"))
    )
    (net (code "60") (name "MIO4") (class "Default")
      (node (ref "D1") (pin "3") (pinfunction "SIO2_3") (pintype "passive"))
      (node (ref "DD1") (pin "E4") (pinfunction "PS_MIO4_500_E4") (pintype "passive"))
      (node (ref "R151") (pin "2") (pinfunction "2_2") (pintype "passive"))
    )
    (net (code "61") (name "MIO5") (class "Default")
      (node (ref "D1") (pin "7") (pinfunction "SIO3_7") (pintype "passive"))
      (node (ref "DD1") (pin "A3") (pinfunction "PS_MIO5_500_A3") (pintype "passive"))
      (node (ref "R12") (pin "2") (pinfunction "2_2") (pintype "passive"))
    )
    (net (code "62") (name "MIO6") (class "Default")
      (node (ref "D1") (pin "6") (pinfunction "CLK_6") (pintype "passive"))
      (node (ref "DD1") (pin "A4") (pinfunction "PS_MIO6_500_A4") (pintype "passive"))
      (node (ref "R156") (pin "2") (pinfunction "2_2") (pintype "passive"))
    )
    (net (code "63") (name "Net-(A1-IN+)") (class "Default")
      (node (ref "A1") (pin "2") (pinfunction "IN+_2") (pintype "passive"))
      (node (ref "C76") (pin "2") (pinfunction "2_2") (pintype "passive"))
      (node (ref "C78") (pin "2") (pinfunction "2_2") (pintype "passive"))
      (node (ref "L10") (pin "2") (pinfunction "2_2") (pintype "passive"))
    )
    (net (code "64") (name "Net-(A1-OUT+)") (class "Default")
      (node (ref "A1") (pin "4") (pinfunction "OUT+_4") (pintype "passive"))
      (node (ref "C82") (pin "2") (pinfunction "2_2") (pintype "passive"))
      (node (ref "C83") (pin "2") (pinfunction "2_2") (pintype "passive"))
      (node (ref "DD4") (pin "16") (pinfunction "VCC2_16") (pintype "passive"))
      (node (ref "R40") (pin "2") (pinfunction "2_2") (pintype "passive"))
    )
    (net (code "65") (name "Net-(D1-~{CS})") (class "Default")
      (node (ref "D1") (pin "1") (pinfunction "~{CS}_1") (pintype "passive"))
      (node (ref "DD1") (pin "A1") (pinfunction "PS_MIO1_500_A1") (pintype "passive"))
      (node (ref "R22") (pin "1") (pinfunction "1_1") (pintype "passive"))
    )
    (net (code "66") (name "Net-(D2-~{WP})") (class "Default")
      (node (ref "D2") (pin "3") (pinfunction "~{WP}_3") (pintype "passive"))
      (node (ref "R26") (pin "2") (pinfunction "2_2") (pintype "passive"))
    )
    (net (code "67") (name "Net-(DD1A-CFGBVS_0)") (class "Default")
      (node (ref "DD1") (pin "T13") (pinfunction "CFGBVS_0_T13") (pintype "passive"))
      (node (ref "R59") (pin "1") (pinfunction "1_1") (pintype "passive"))
    )
    (net (code "68") (name "Net-(DD1A-DONE_0)") (class "Default")
      (node (ref "DD1") (pin "T12") (pinfunction "DONE_0_T12") (pintype "passive"))
      (node (ref "HL1") (pin "1") (pinfunction "A_1") (pintype "passive"))
      (node (ref "R23") (pin "2") (pinfunction "2_2") (pintype "passive"))
    )
    (net (code "69") (name "Net-(DD1A-INIT_B_0)") (class "Default")
      (node (ref "DD1") (pin "T14") (pinfunction "INIT_B_0_T14") (pintype "passive"))
      (node (ref "R24") (pin "2") (pinfunction "2_2") (pintype "passive"))
    )
    (net (code "70") (name "Net-(DD1A-PROGRAM_B_0)") (class "Default")
      (node (ref "DD1") (pin "T11") (pinfunction "PROGRAM_B_0_T11") (pintype "passive"))
      (node (ref "R25") (pin "2") (pinfunction "2_2") (pintype "passive"))
    )
    (net (code "71") (name "Net-(DD1F-PS_CLK_500)") (class "Default")
      (node (ref "DD1") (pin "F7") (pinfunction "PS_CLK_500_F7") (pintype "passive"))
      (node (ref "G1") (pin "3") (pinfunction "OUT_3") (pintype "passive"))
    )
    (net (code "72") (name "Net-(DD1G-PS_MIO26_501)") (class "Default")
      (node (ref "DD1") (pin "A13") (pinfunction "PS_MIO26_501_A13") (pintype "passive"))
      (node (ref "X1") (pin "1") (pinfunction "~_1") (pintype "passive"))
    )
    (net (code "73") (name "Net-(DD1G-PS_MIO28_501)") (class "Default")
      (node (ref "DD1") (pin "A12") (pinfunction "PS_MIO28_501_A12") (pintype "passive"))
      (node (ref "X2") (pin "1") (pinfunction "~_1") (pintype "passive"))
    )
    (net (code "74") (name "Net-(DD1G-PS_SRST_B_501)") (class "Default")
      (node (ref "DD1") (pin "C9") (pinfunction "PS_SRST_B_501_C9") (pintype "passive"))
      (node (ref "R27") (pin "1") (pinfunction "1_1") (pintype "passive"))
    )
    (net (code "75") (name "Net-(DD2-DE)") (class "Default")
      (node (ref "C79") (pin "2") (pinfunction "2_2") (pintype "passive"))
      (node (ref "DD2") (pin "1") (pinfunction "VL_1") (pintype "passive"))
      (node (ref "DD2") (pin "14") (pinfunction "VCC_14") (pintype "passive"))
      (node (ref "DD2") (pin "3") (pinfunction "DE_3") (pintype "passive"))
      (node (ref "L12") (pin "2") (pinfunction "2_2") (pintype "passive"))
      (node (ref "R33") (pin "2") (pinfunction "2_2") (pintype "passive"))
    )
    (net (code "76") (name "Net-(DD3-DE)") (class "Default")
      (node (ref "C80") (pin "2") (pinfunction "2_2") (pintype "passive"))
      (node (ref "DD3") (pin "1") (pinfunction "VL_1") (pintype "passive"))
      (node (ref "DD3") (pin "14") (pinfunction "VCC_14") (pintype "passive"))
      (node (ref "DD3") (pin "3") (pinfunction "DE_3") (pintype "passive"))
      (node (ref "L13") (pin "2") (pinfunction "2_2") (pintype "passive"))
      (node (ref "R35") (pin "2") (pinfunction "2_2") (pintype "passive"))
    )
    (net (code "77") (name "Net-(DD4-A)") (class "Default")
      (node (ref "DD4") (pin "14") (pinfunction "A_14") (pintype "input"))
      (node (ref "R40") (pin "1") (pinfunction "1_1") (pintype "passive"))
      (node (ref "R42") (pin "1") (pinfunction "1_1") (pintype "passive"))
    )
    (net (code "78") (name "Net-(DD4-B)") (class "Default")
      (node (ref "DD4") (pin "13") (pinfunction "B_13") (pintype "input"))
      (node (ref "R41") (pin "2") (pinfunction "2_2") (pintype "passive"))
      (node (ref "R43") (pin "1") (pinfunction "1_1") (pintype "passive"))
    )
    (net (code "79") (name "Net-(DD4-DE)") (class "Default")
      (node (ref "C77") (pin "2") (pinfunction "2_2") (pintype "passive"))
      (node (ref "DD4") (pin "1") (pinfunction "VCC1_1") (pintype "passive"))
      (node (ref "DD4") (pin "4") (pinfunction "~{RE}_4") (pintype "input"))
      (node (ref "DD4") (pin "5") (pinfunction "DE_5") (pintype "input"))
      (node (ref "L11") (pin "2") (pinfunction "2_2") (pintype "passive"))
    )
    (net (code "80") (name "Net-(DD5-1A)") (class "Default")
      (node (ref "C85") (pin "2") (pinfunction "2_2") (pintype "passive"))
      (node (ref "DD5") (pin "1") (pinfunction "1A_1") (pintype "input"))
      (node (ref "R44") (pin "1") (pinfunction "1_1") (pintype "passive"))
      (node (ref "R45") (pin "1") (pinfunction "1_1") (pintype "passive"))
      (node (ref "VD2") (pin "1") (pinfunction "A_1") (pintype "passive"))
    )
    (net (code "81") (name "Net-(DD5-2A)") (class "Default")
      (node (ref "DD5") (pin "3") (pinfunction "2A_3") (pintype "input"))
      (node (ref "R37") (pin "1") (pinfunction "1_1") (pintype "passive"))
      (node (ref "VD1") (pin "1") (pinfunction "A_1") (pintype "passive"))
    )
    (net (code "82") (name "Net-(G1-VDD)") (class "Default")
      (node (ref "C65") (pin "2") (pinfunction "2_2") (pintype "passive"))
      (node (ref "G1") (pin "4") (pinfunction "VDD_4") (pintype "passive"))
      (node (ref "L9") (pin "2") (pinfunction "2_2") (pintype "passive"))
    )
    (net (code "83") (name "Net-(L14-Pad2)") (class "Default")
      (node (ref "L14") (pin "2") (pinfunction "2_2") (pintype "passive"))
      (node (ref "R42") (pin "2") (pinfunction "2_2") (pintype "passive"))
      (node (ref "R46") (pin "1") (pinfunction "1_1") (pintype "passive"))
    )
    (net (code "84") (name "Net-(L14-Pad3)") (class "Default")
      (node (ref "L14") (pin "3") (pinfunction "3_3") (pintype "passive"))
      (node (ref "R43") (pin "2") (pinfunction "2_2") (pintype "passive"))
      (node (ref "R46") (pin "2") (pinfunction "2_2") (pintype "passive"))
    )
    (net (code "85") (name "Net-(R12-Pad1)") (class "Default")
      (node (ref "R12") (pin "1") (pinfunction "1_1") (pintype "passive"))
      (node (ref "XP7") (pin "2") (pinfunction "2_2") (pintype "passive"))
    )
    (net (code "86") (name "Net-(VU1-A)") (class "Default")
      (node (ref "R38") (pin "2") (pinfunction "2_2") (pintype "passive"))
      (node (ref "VU1") (pin "1") (pinfunction "A_1") (pintype "passive"))
    )
    (net (code "87") (name "Net-(VU1-C)") (class "Default")
      (node (ref "DA8") (pin "1") (pintype "passive"))
      (node (ref "F1") (pin "2") (pinfunction "2_2") (pintype "passive"))
      (node (ref "VU1") (pin "4") (pinfunction "C_4") (pintype "passive"))
    )
    (net (code "88") (name "Net-(VU2-A)") (class "Default")
      (node (ref "R39") (pin "2") (pinfunction "2_2") (pintype "passive"))
      (node (ref "VU2") (pin "1") (pinfunction "A_1") (pintype "passive"))
    )
    (net (code "89") (name "Net-(VU2-C)") (class "Default")
      (node (ref "DA9") (pin "1") (pintype "passive"))
      (node (ref "F3") (pin "2") (pinfunction "2_2") (pintype "passive"))
      (node (ref "VU2") (pin "4") (pinfunction "C_4") (pintype "passive"))
    )
    (net (code "90") (name "OUT_422A") (class "Default")
      (node (ref "L14") (pin "1") (pinfunction "1_1") (pintype "passive"))
      (node (ref "XS3") (pin "11") (pinfunction "11_11") (pintype "passive"))
    )
    (net (code "91") (name "OUT_422B") (class "Default")
      (node (ref "L14") (pin "4") (pinfunction "4_4") (pintype "passive"))
      (node (ref "XS3") (pin "12") (pinfunction "12_12") (pintype "passive"))
    )
    (net (code "92") (name "OUT_422Y") (class "Default")
      (node (ref "DD4") (pin "11") (pinfunction "Y_11") (pintype "output"))
      (node (ref "XS3") (pin "14") (pinfunction "14_14") (pintype "passive"))
    )
    (net (code "93") (name "OUT_422Z") (class "Default")
      (node (ref "DD4") (pin "12") (pinfunction "Z_12") (pintype "output"))
      (node (ref "XS3") (pin "13") (pinfunction "13_13") (pintype "passive"))
    )
    (net (code "94") (name "OUT_GND") (class "Default")
      (node (ref "A1") (pin "3") (pinfunction "OUT-_3") (pintype "passive"))
      (node (ref "C82") (pin "1") (pinfunction "1_1") (pintype "passive"))
      (node (ref "C83") (pin "1") (pinfunction "1_1") (pintype "passive"))
      (node (ref "DD4") (pin "10") (pinfunction "GND2_10") (pintype "passive"))
      (node (ref "DD4") (pin "15") (pinfunction "GND2_15") (pintype "passive"))
      (node (ref "DD4") (pin "9") (pinfunction "GND2_9") (pintype "passive"))
      (node (ref "R41") (pin "1") (pinfunction "1_1") (pintype "passive"))
      (node (ref "XS3") (pin "15") (pinfunction "15_15") (pintype "passive"))
      (node (ref "XS3") (pin "3") (pinfunction "3_3") (pintype "passive"))
    )
    (net (code "95") (name "PG_ALL") (class "Default")
      (node (ref "C67") (pin "2") (pinfunction "2_2") (pintype "passive"))
      (node (ref "DD1") (pin "B5") (pinfunction "PS_POR_B_500_B5") (pintype "passive"))
      (node (ref "R28") (pin "1") (pinfunction "1_1") (pintype "passive"))
    )
    (net (code "96") (name "PTT_IN") (class "Default")
      (node (ref "C86") (pin "2") (pinfunction "2_2") (pintype "passive"))
      (node (ref "VD2") (pin "3") (pinfunction "K_3") (pintype "passive"))
      (node (ref "XP3") (pin "14") (pinfunction "14_14") (pintype "passive"))
    )
    (net (code "97") (name "PTT_OUT_N") (class "Default")
      (node (ref "DA8") (pin "2") (pintype "passive"))
      (node (ref "VU1") (pin "3") (pinfunction "E_3") (pintype "passive"))
      (node (ref "XS3") (pin "2") (pinfunction "2_2") (pintype "passive"))
    )
    (net (code "98") (name "PTT_OUT_P") (class "Default")
      (node (ref "F1") (pin "1") (pinfunction "1_1") (pintype "passive"))
      (node (ref "XS3") (pin "1") (pinfunction "1_1") (pintype "passive"))
    )
    (net (code "99") (name "PWR_EN") (class "Default")
      (node (ref "XP3") (pin "15") (pinfunction "15_15") (pintype "passive"))
    )
    (net (code "100") (name "TUNE_OUT_N") (class "Default")
      (node (ref "DA9") (pin "2") (pintype "passive"))
      (node (ref "VU2") (pin "3") (pinfunction "E_3") (pintype "passive"))
      (node (ref "XS3") (pin "5") (pinfunction "5_5") (pintype "passive"))
    )
    (net (code "101") (name "TUNE_OUT_P") (class "Default")
      (node (ref "F3") (pin "1") (pinfunction "1_1") (pintype "passive"))
      (node (ref "XS3") (pin "4") (pinfunction "4_4") (pintype "passive"))
    )
    (net (code "102") (name "VCC_12V0") (class "Default")
      (node (ref "XP3") (pin "2") (pinfunction "2_2") (pintype "passive"))
      (node (ref "XP3") (pin "3") (pinfunction "3_3") (pintype "passive"))
    )
    (net (code "103") (name "VDD_1V8") (class "Default")
      (node (ref "DD1") (pin "K11") (pinfunction "VCCADC_0_K11") (pintype "passive"))
    )
    (net (code "104") (name "VDD_3V3") (class "Default")
      (node (ref "C66") (pin "2") (pinfunction "2_2") (pintype "passive"))
      (node (ref "C68") (pin "2") (pinfunction "2_2") (pintype "passive"))
      (node (ref "C69") (pin "2") (pinfunction "2_2") (pintype "passive"))
      (node (ref "C71") (pin "2") (pinfunction "2_2") (pintype "passive"))
      (node (ref "C75") (pin "2") (pinfunction "2_2") (pintype "passive"))
      (node (ref "C81") (pin "2") (pinfunction "2_2") (pintype "passive"))
      (node (ref "D1") (pin "8") (pinfunction "VCC_8") (pintype "passive"))
      (node (ref "D2") (pin "7") (pinfunction "~{HOLD}_7") (pintype "passive"))
      (node (ref "D2") (pin "8") (pinfunction "VCC_8") (pintype "passive"))
      (node (ref "DD1") (pin "A10") (pinfunction "VCCO_MIO1_501_A10") (pintype "passive"))
      (node (ref "DD1") (pin "B13") (pinfunction "VCCO_MIO1_501_B13") (pintype "passive"))
      (node (ref "DD1") (pin "B3") (pinfunction "VCCO_MIO0_500_B3") (pintype "passive"))
      (node (ref "DD1") (pin "C6") (pinfunction "VCCO_MIO0_500_C6") (pintype "passive"))
      (node (ref "DD1") (pin "D9") (pinfunction "VCCO_MIO1_501_D9") (pintype "passive"))
      (node (ref "DD1") (pin "E12") (pinfunction "VCCO_MIO1_501_E12") (pintype "passive"))
      (node (ref "DD1") (pin "G9") (pinfunction "VCCBATT_0_G9") (pintype "passive"))
      (node (ref "DD1") (pin "R12") (pinfunction "VCCO_0_R12") (pintype "passive"))
      (node (ref "DD1") (pin "T10") (pinfunction "RSVDVCC3_T10") (pintype "passive"))
      (node (ref "DD1") (pin "T7") (pinfunction "RSVDVCC1_T7") (pintype "passive"))
      (node (ref "DD1") (pin "T8") (pinfunction "RSVDVCC2_T8") (pintype "passive"))
      (node (ref "DD5") (pin "5") (pinfunction "VCC_5") (pintype "passive"))
      (node (ref "L11") (pin "1") (pinfunction "1_1") (pintype "passive"))
      (node (ref "L12") (pin "1") (pinfunction "1_1") (pintype "passive"))
      (node (ref "L13") (pin "1") (pinfunction "1_1") (pintype "passive"))
      (node (ref "L9") (pin "1") (pinfunction "1_1") (pintype "passive"))
      (node (ref "R20") (pin "1") (pinfunction "1_1") (pintype "passive"))
      (node (ref "R21") (pin "1") (pinfunction "1_1") (pintype "passive"))
      (node (ref "R22") (pin "2") (pinfunction "2_2") (pintype "passive"))
      (node (ref "R23") (pin "1") (pinfunction "1_1") (pintype "passive"))
      (node (ref "R24") (pin "1") (pinfunction "1_1") (pintype "passive"))
      (node (ref "R25") (pin "1") (pinfunction "1_1") (pintype "passive"))
      (node (ref "R26") (pin "1") (pinfunction "1_1") (pintype "passive"))
      (node (ref "R27") (pin "2") (pinfunction "2_2") (pintype "passive"))
      (node (ref "R28") (pin "2") (pinfunction "2_2") (pintype "passive"))
      (node (ref "R31") (pin "1") (pinfunction "1_1") (pintype "passive"))
      (node (ref "R32") (pin "1") (pinfunction "1_1") (pintype "passive"))
      (node (ref "R37") (pin "2") (pinfunction "2_2") (pintype "passive"))
      (node (ref "R59") (pin "2") (pinfunction "2_2") (pintype "passive"))
      (node (ref "XP2") (pin "2") (pinfunction "2_2") (pintype "passive"))
      (node (ref "XP7") (pin "3") (pinfunction "3_3") (pintype "passive"))
    )
    (net (code "105") (name "VDD_5V0") (class "Default")
      (node (ref "L10") (pin "1") (pinfunction "1_1") (pintype "passive"))
      (node (ref "R44") (pin "2") (pinfunction "2_2") (pintype "passive"))
      (node (ref "XP4") (pin "2") (pinfunction "2_2") (pintype "passive"))
    )
    (net (code "106") (name "VMODE0") (class "Default")
      (node (ref "DD1") (pin "D5") (pinfunction "PS_MIO7_500_D5") (pintype "passive"))
      (node (ref "R158") (pin "2") (pinfunction "2_2") (pintype "passive"))
    )
    (net (code "107") (name "VMODE1") (class "Default")
      (node (ref "DD1") (pin "E5") (pinfunction "PS_MIO8_500_E5") (pintype "passive"))
      (node (ref "R159") (pin "2") (pinfunction "2_2") (pintype "passive"))
    )
    (net (code "108") (name "unconnected-(DD1A-VN_0-PadM12)") (class "Default")
      (node (ref "DD1") (pin "M12") (pinfunction "VN_0_M12") (pintype "passive"))
    )
    (net (code "109") (name "unconnected-(DD1A-VP_0-PadL11)") (class "Default")
      (node (ref "DD1") (pin "L11") (pinfunction "VP_0_L11") (pintype "passive"))
    )
    (net (code "110") (name "unconnected-(DD1F-PS_MIO0_500-PadG6)") (class "Default")
      (node (ref "DD1") (pin "G6") (pinfunction "PS_MIO0_500_G6") (pintype "passive"))
    )
    (net (code "111") (name "unconnected-(DD1F-PS_MIO9_500-PadC4)") (class "Default")
      (node (ref "DD1") (pin "C4") (pinfunction "PS_MIO9_500_C4") (pintype "passive"))
    )
    (net (code "112") (name "unconnected-(DD1G-PS_MIO17_501-PadE9)") (class "Default")
      (node (ref "DD1") (pin "E9") (pinfunction "PS_MIO17_501_E9") (pintype "passive"))
    )
    (net (code "113") (name "unconnected-(DD1G-PS_MIO18_501-PadA7)") (class "Default")
      (node (ref "DD1") (pin "A7") (pinfunction "PS_MIO18_501_A7") (pintype "passive"))
    )
    (net (code "114") (name "unconnected-(DD1G-PS_MIO19_501-PadE10)") (class "Default")
      (node (ref "DD1") (pin "E10") (pinfunction "PS_MIO19_501_E10") (pintype "passive"))
    )
    (net (code "115") (name "unconnected-(DD1G-PS_MIO20_501-PadA8)") (class "Default")
      (node (ref "DD1") (pin "A8") (pinfunction "PS_MIO20_501_A8") (pintype "passive"))
    )
    (net (code "116") (name "unconnected-(DD1G-PS_MIO24_501-PadB7)") (class "Default")
      (node (ref "DD1") (pin "B7") (pinfunction "PS_MIO24_501_B7") (pintype "passive"))
    )
    (net (code "117") (name "unconnected-(DD1G-PS_MIO25_501-PadF12)") (class "Default")
      (node (ref "DD1") (pin "F12") (pinfunction "PS_MIO25_501_F12") (pintype "passive"))
    )
    (net (code "118") (name "unconnected-(DD1G-PS_MIO27_501-PadD7)") (class "Default")
      (node (ref "DD1") (pin "D7") (pinfunction "PS_MIO27_501_D7") (pintype "passive"))
    )
    (net (code "119") (name "unconnected-(DD1G-PS_MIO29_501-PadE8)") (class "Default")
      (node (ref "DD1") (pin "E8") (pinfunction "PS_MIO29_501_E8") (pintype "passive"))
    )
    (net (code "120") (name "unconnected-(DD1G-PS_MIO30_501-PadA11)") (class "Default")
      (node (ref "DD1") (pin "A11") (pinfunction "PS_MIO30_501_A11") (pintype "passive"))
    )
    (net (code "121") (name "unconnected-(DD1G-PS_MIO31_501-PadF9)") (class "Default")
      (node (ref "DD1") (pin "F9") (pinfunction "PS_MIO31_501_F9") (pintype "passive"))
    )
    (net (code "122") (name "unconnected-(DD1G-PS_MIO32_501-PadC7)") (class "Default")
      (node (ref "DD1") (pin "C7") (pinfunction "PS_MIO32_501_C7") (pintype "passive"))
    )
    (net (code "123") (name "unconnected-(DD1G-PS_MIO39_501-PadC13)") (class "Default")
      (node (ref "DD1") (pin "C13") (pinfunction "PS_MIO39_501_C13") (pintype "passive"))
    )
    (net (code "124") (name "unconnected-(DD1G-PS_MIO40_501-PadE14)") (class "Default")
      (node (ref "DD1") (pin "E14") (pinfunction "PS_MIO40_501_E14") (pintype "passive"))
    )
    (net (code "125") (name "unconnected-(DD1G-PS_MIO41_501-PadC8)") (class "Default")
      (node (ref "DD1") (pin "C8") (pinfunction "PS_MIO41_501_C8") (pintype "passive"))
    )
    (net (code "126") (name "unconnected-(DD1G-PS_MIO42_501-PadD8)") (class "Default")
      (node (ref "DD1") (pin "D8") (pinfunction "PS_MIO42_501_D8") (pintype "passive"))
    )
    (net (code "127") (name "unconnected-(DD1G-PS_MIO43_501-PadB11)") (class "Default")
      (node (ref "DD1") (pin "B11") (pinfunction "PS_MIO43_501_B11") (pintype "passive"))
    )
    (net (code "128") (name "unconnected-(DD1G-PS_MIO44_501-PadE13)") (class "Default")
      (node (ref "DD1") (pin "E13") (pinfunction "PS_MIO44_501_E13") (pintype "passive"))
    )
    (net (code "129") (name "unconnected-(DD1G-PS_MIO45_501-PadB9)") (class "Default")
      (node (ref "DD1") (pin "B9") (pinfunction "PS_MIO45_501_B9") (pintype "passive"))
    )
    (net (code "130") (name "unconnected-(DD1G-PS_MIO46_501-PadD12)") (class "Default")
      (node (ref "DD1") (pin "D12") (pinfunction "PS_MIO46_501_D12") (pintype "passive"))
    )
    (net (code "131") (name "unconnected-(DD1G-PS_MIO47_501-PadB10)") (class "Default")
      (node (ref "DD1") (pin "B10") (pinfunction "PS_MIO47_501_B10") (pintype "passive"))
    )
    (net (code "132") (name "unconnected-(DD1G-PS_MIO50_501-PadD13)") (class "Default")
      (node (ref "DD1") (pin "D13") (pinfunction "PS_MIO50_501_D13") (pintype "passive"))
    )
    (net (code "133") (name "unconnected-(DD1G-PS_MIO51_501-PadC10)") (class "Default")
      (node (ref "DD1") (pin "C10") (pinfunction "PS_MIO51_501_C10") (pintype "passive"))
    )
    (net (code "134") (name "unconnected-(DD1G-PS_MIO52_501-PadD10)") (class "Default")
      (node (ref "DD1") (pin "D10") (pinfunction "PS_MIO52_501_D10") (pintype "passive"))
    )
    (net (code "135") (name "unconnected-(DD1G-PS_MIO53_501-PadC12)") (class "Default")
      (node (ref "DD1") (pin "C12") (pinfunction "PS_MIO53_501_C12") (pintype "passive"))
    )
    (net (code "136") (name "unconnected-(DD1G-PS_MIO_VREF_501-PadF8)") (class "Default")
      (node (ref "DD1") (pin "F8") (pinfunction "PS_MIO_VREF_501_F8") (pintype "passive"))
    )
    (net (code "137") (name "unconnected-(G1-CTRL-Pad1)") (class "Default")
      (node (ref "G1") (pin "1") (pinfunction "CTRL_1") (pintype "passive"))
    )
    (net (code "138") (name "unconnected-(XP2-Pad12)") (class "Default")
      (node (ref "XP2") (pin "12") (pinfunction "12_12") (pintype "passive"))
    )
    (net (code "139") (name "unconnected-(XP2-Pad14)") (class "Default")
      (node (ref "XP2") (pin "14") (pinfunction "14_14") (pintype "passive"))
    )
    (net (code "140") (name "unconnected-(XS3-Pad6)") (class "Default")
      (node (ref "XS3") (pin "6") (pinfunction "6_6") (pintype "passive"))
    )
    (net (code "141") (name "unconnected-(XS3-Pad7)") (class "Default")
      (node (ref "XS3") (pin "7") (pinfunction "7_7") (pintype "passive"))
    )
    (net (code "142") (name "unconnected-(XS3-Pad8)") (class "Default")
      (node (ref "XS3") (pin "8") (pinfunction "8_8") (pintype "passive"))
    )
    (net (code "143") (name "unconnected-(XS3-Pad9)") (class "Default")
      (node (ref "XS3") (pin "9") (pinfunction "9_9") (pintype "passive"))
    )
    (net (code "144") (name "unconnected-(XS3-Pad10)") (class "Default")
      (node (ref "XS3") (pin "10") (pinfunction "10_10") (pintype "passive"))
    )
    (net (code "145") (name "unconnected-(Z1-IN-Pad2)") (class "Default")
      (node (ref "Z1") (pin "2") (pinfunction "IN_2") (pintype "passive"))
    )
    (net (code "146") (name "unconnected-(Z1-IN-Pad3)") (class "Default")
      (node (ref "Z1") (pin "3") (pinfunction "IN_3") (pintype "passive"))
    )
    (net (code "147") (name "unconnected-(Z1-OUT-Pad6)") (class "Default")
      (node (ref "Z1") (pin "6") (pinfunction "OUT_6") (pintype "passive"))
    )
    (net (code "148") (name "unconnected-(Z1-OUT-Pad7)") (class "Default")
      (node (ref "Z1") (pin "7") (pinfunction "OUT_7") (pintype "passive"))
    )
  )
)
